# MergeRev4_0.net
KiCad netlist of a schematic drawn in Altium Designer
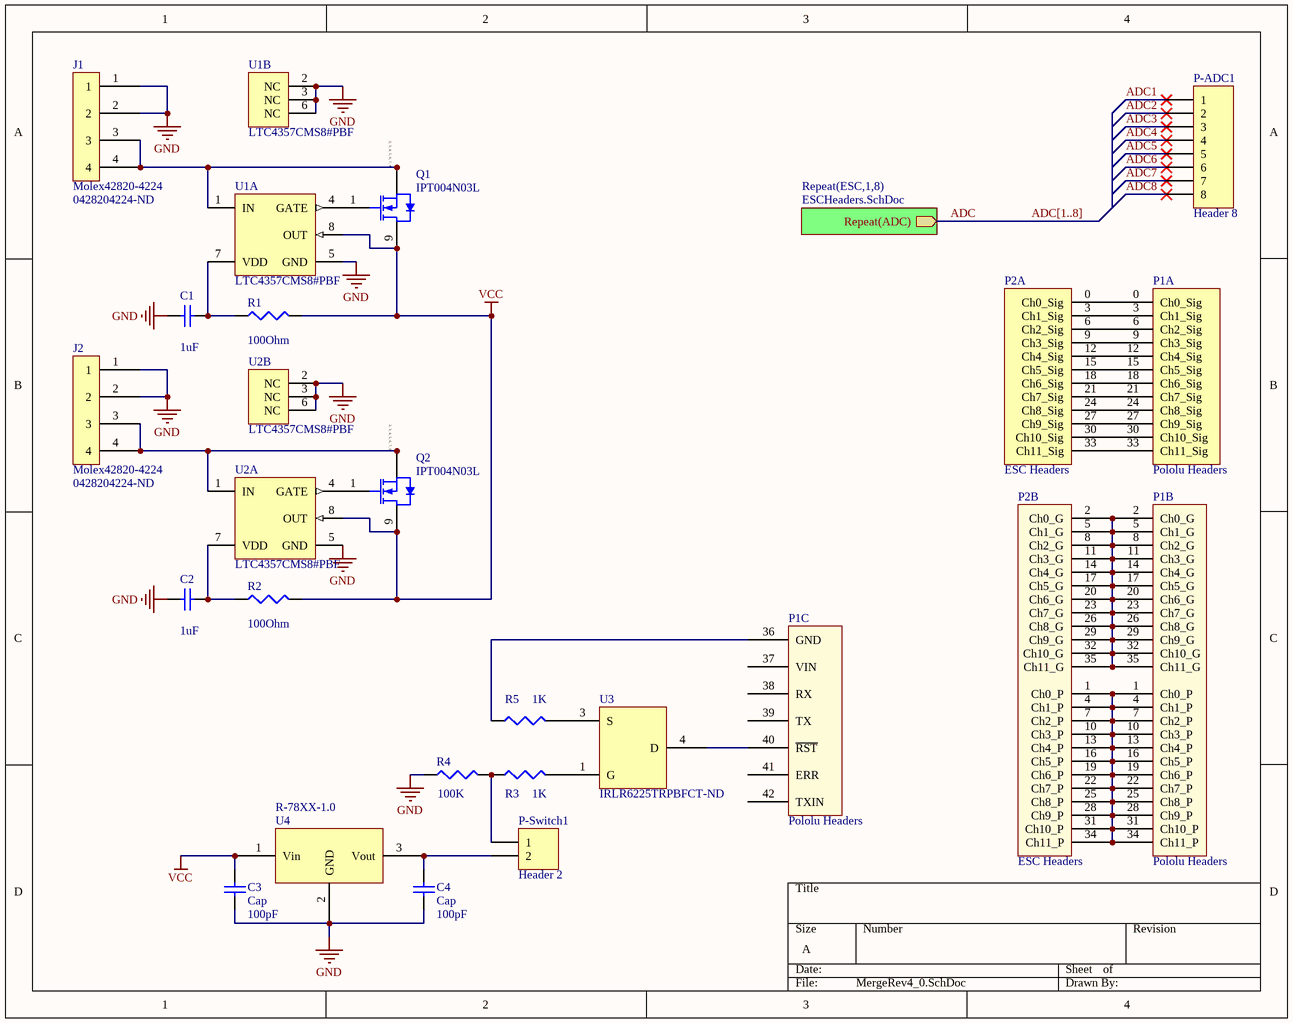
[diagram p0: MergeRev4_0.SchDoc]

(export (version "E")
  (design (tool "Eeschema 10.0.6"))
  (components
    (comp (ref "C1")
      (value "1uF")
      (footprint "C1206")
      (description "Capacitor (Semiconductor SIM Model)")
      (fields (field (name "Comment") "Cap Semi") (field (name "PUBLISHER") "Altium Limited"))
      (libsource (lib "Miscellaneous Devices") (part "Cap Semi"))
    )
    (comp (ref "C2")
      (value "1uF")
      (footprint "C1206")
      (description "Capacitor (Semiconductor SIM Model)")
      (fields (field (name "Comment") "Cap Semi") (field (name "PUBLISHER") "Altium Limited"))
      (libsource (lib "Miscellaneous Devices") (part "Cap Semi"))
    )
    (comp (ref "C3")
      (value "Cap")
      (footprint "1608[0603]")
      (description "Capacitor")
      (fields (field (name "ALTIUM_VALUE") "100pF") (field (name "PUBLISHER") "Altium Limited"))
      (libsource (lib "Miscellaneous Devices") (part "Cap"))
    )
    (comp (ref "C4")
      (value "Cap")
      (footprint "1608[0603]")
      (description "Capacitor")
      (fields (field (name "ALTIUM_VALUE") "100pF") (field (name "PUBLISHER") "Altium Limited"))
      (libsource (lib "Miscellaneous Devices") (part "Cap"))
    )
    (comp (ref "J1")
      (value "Molex42820-4224")
      (footprint "Molex42820-4224")
      (fields (field (name "SUPPLIER PART NUMBER 1") "0428204224-ND"))
      (libsource (lib "Molex42820-4224") (part "Molex42820-4224"))
    )
    (comp (ref "J2")
      (value "Molex42820-4224")
      (footprint "Molex42820-4224")
      (fields (field (name "SUPPLIER PART NUMBER 1") "0428204224-ND"))
      (libsource (lib "Molex42820-4224") (part "Molex42820-4224"))
    )
    (comp (ref "P-ADC1")
      (value "Header 8")
      (footprint "HDR1X8")
      (description "Header, 8-Pin")
      (fields (field (name "PUBLISHER") "Altium Limited"))
      (libsource (lib "Miscellaneous Connectors") (part "Header 8"))
    )
    (comp (ref "P-Switch1")
      (value "Header 2")
      (footprint "HDR1X2")
      (description "Header, 2-Pin")
      (fields (field (name "PUBLISHER") "Altium Limited"))
      (libsource (lib "Miscellaneous Connectors") (part "Header 2"))
    )
    (comp (ref "P1")
      (value "Pololu Headers")
      (footprint "Pololu Headers")
      (libsource (lib "MergeRev3_0") (part "Pololu Headers"))
    )
    (comp (ref "P2")
      (value "ESC Headers")
      (footprint "Pololu Headers")
      (libsource (lib "") (part "Pololu Headers_1"))
    )
    (comp (ref "Q1")
      (value "IPT004N03L")
      (footprint "INF-PG-HSOF-8-1_V")
      (description "N-Channel OptiMOS(TM) Power-MOSFET, 30 V VDS, 300 A ID, -55 to 175 degC, PG-HSOF-8, Reel, Green")
      (fields (field (name "MANUFACTURER") "Infineon"))
      (libsource (lib "MergeRev3_0") (part "IPT004N03L"))
    )
    (comp (ref "Q2")
      (value "IPT004N03L")
      (footprint "INF-PG-HSOF-8-1_V")
      (description "N-Channel OptiMOS(TM) Power-MOSFET, 30 V VDS, 300 A ID, -55 to 175 degC, PG-HSOF-8, Reel, Green")
      (fields (field (name "MANUFACTURER") "Infineon"))
      (libsource (lib "MergeRev3_0") (part "IPT004N03L"))
    )
    (comp (ref "R1")
      (value "100Ohm")
      (footprint "J1-0603")
      (description "Resistor")
      (fields (field (name "Comment") "Res3") (field (name "PUBLISHER") "Altium Limited"))
      (libsource (lib "Miscellaneous Devices") (part "Res3"))
    )
    (comp (ref "R2")
      (value "100Ohm")
      (footprint "J1-0603")
      (description "Resistor")
      (fields (field (name "Comment") "Res3") (field (name "PUBLISHER") "Altium Limited"))
      (libsource (lib "Miscellaneous Devices") (part "Res3"))
    )
    (comp (ref "R3")
      (value "1K")
      (footprint "J1-0603")
      (description "Resistor")
      (fields (field (name "Comment") "Res3") (field (name "PUBLISHER") "Altium Limited"))
      (libsource (lib "Miscellaneous Devices") (part "Res3"))
    )
    (comp (ref "R4")
      (value "100K")
      (footprint "J1-0603")
      (description "Resistor")
      (fields (field (name "Comment") "Res3") (field (name "PUBLISHER") "Altium Limited"))
      (libsource (lib "Miscellaneous Devices") (part "Res3"))
    )
    (comp (ref "R5")
      (value "1K")
      (footprint "J1-0603")
      (description "Resistor")
      (fields (field (name "Comment") "Res3") (field (name "PUBLISHER") "Altium Limited"))
      (libsource (lib "Miscellaneous Devices") (part "Res3"))
    )
    (comp (ref "U1")
      (value "LTC4357CMS8#PBF")
      (footprint "LT-MS8-8_N")
      (fields (field (name "MANUFACTURER") "Linear Technology"))
      (libsource (lib "MergeRev3_0") (part "LTC4357CMS8#PBF"))
    )
    (comp (ref "U2")
      (value "LTC4357CMS8#PBF")
      (footprint "LT-MS8-8_N")
      (fields (field (name "MANUFACTURER") "Linear Technology"))
      (libsource (lib "MergeRev3_0") (part "LTC4357CMS8#PBF"))
    )
    (comp (ref "U3")
      (value "IRLR6225TRPBFCT-ND")
      (footprint "IRLR6225_DT")
      (libsource (lib "IRLR6225_DT") (part "IRLR6225TRPBFCT-ND"))
    )
    (comp (ref "U4")
      (value "R-78XX-1.0")
      (footprint "R-785.0-1.0")
      (libsource (lib "RECOM-Reg") (part "R-78XX-1.0"))
    )
  )
  (nets
    (net (code "2") (name "/ADC1") (class "Default")
      (node (ref "P-ADC1") (pin "1") (pinfunction "1_1") (pintype "passive+no_connect"))
    )
    (net (code "3") (name "/ADC2") (class "Default")
      (node (ref "P-ADC1") (pin "2") (pinfunction "2_2") (pintype "passive+no_connect"))
    )
    (net (code "4") (name "/ADC3") (class "Default")
      (node (ref "P-ADC1") (pin "3") (pinfunction "3_3") (pintype "passive+no_connect"))
    )
    (net (code "5") (name "/ADC4") (class "Default")
      (node (ref "P-ADC1") (pin "4") (pinfunction "4_4") (pintype "passive+no_connect"))
    )
    (net (code "6") (name "/ADC5") (class "Default")
      (node (ref "P-ADC1") (pin "5") (pinfunction "5_5") (pintype "passive+no_connect"))
    )
    (net (code "7") (name "/ADC6") (class "Default")
      (node (ref "P-ADC1") (pin "6") (pinfunction "6_6") (pintype "passive+no_connect"))
    )
    (net (code "8") (name "/ADC7") (class "Default")
      (node (ref "P-ADC1") (pin "7") (pinfunction "7_7") (pintype "passive+no_connect"))
    )
    (net (code "9") (name "/ADC8") (class "Default")
      (node (ref "P-ADC1") (pin "8") (pinfunction "8_8") (pintype "passive+no_connect"))
    )
    (net (code "11") (name "GND") (class "Default")
      (node (ref "C1") (pin "1") (pinfunction "1_1") (pintype "passive"))
      (node (ref "C2") (pin "1") (pinfunction "1_1") (pintype "passive"))
      (node (ref "C3") (pin "1") (pinfunction "1_1") (pintype "passive"))
      (node (ref "C4") (pin "1") (pinfunction "1_1") (pintype "passive"))
      (node (ref "J1") (pin "1") (pinfunction "1_1") (pintype "power_in"))
      (node (ref "J1") (pin "2") (pinfunction "2_2") (pintype "power_in"))
      (node (ref "J2") (pin "1") (pinfunction "1_1") (pintype "power_in"))
      (node (ref "J2") (pin "2") (pinfunction "2_2") (pintype "power_in"))
      (node (ref "R4") (pin "1") (pinfunction "1_1") (pintype "passive"))
      (node (ref "U1") (pin "2") (pinfunction "NC_2") (pintype "passive"))
      (node (ref "U1") (pin "3") (pinfunction "NC_3") (pintype "passive"))
      (node (ref "U1") (pin "5") (pinfunction "GND_5") (pintype "power_in"))
      (node (ref "U1") (pin "6") (pinfunction "NC_6") (pintype "passive"))
      (node (ref "U2") (pin "2") (pinfunction "NC_2") (pintype "passive"))
      (node (ref "U2") (pin "3") (pinfunction "NC_3") (pintype "passive"))
      (node (ref "U2") (pin "5") (pinfunction "GND_5") (pintype "power_in"))
      (node (ref "U2") (pin "6") (pinfunction "NC_6") (pintype "passive"))
      (node (ref "U4") (pin "2") (pinfunction "GND_2") (pintype "passive"))
    )
    (net (code "12") (name "Net-(P-Switch1-Pad1)") (class "Default")
      (node (ref "P-Switch1") (pin "1") (pinfunction "1_1") (pintype "passive"))
      (node (ref "R3") (pin "1") (pinfunction "1_1") (pintype "passive"))
      (node (ref "R4") (pin "2") (pinfunction "2_2") (pintype "passive"))
    )
    (net (code "13") (name "Net-(P1A-Ch0_Sig)") (class "Default")
      (node (ref "P1") (pin "0") (pinfunction "Ch0_Sig_0") (pintype "passive"))
      (node (ref "P2") (pin "0") (pinfunction "Ch0_Sig_0") (pintype "passive"))
    )
    (net (code "14") (name "Net-(P1A-Ch1_Sig)") (class "Default")
      (node (ref "P1") (pin "3") (pinfunction "Ch1_Sig_3") (pintype "passive"))
      (node (ref "P2") (pin "3") (pinfunction "Ch1_Sig_3") (pintype "passive"))
    )
    (net (code "15") (name "Net-(P1A-Ch2_Sig)") (class "Default")
      (node (ref "P1") (pin "6") (pinfunction "Ch2_Sig_6") (pintype "passive"))
      (node (ref "P2") (pin "6") (pinfunction "Ch2_Sig_6") (pintype "passive"))
    )
    (net (code "16") (name "Net-(P1A-Ch3_Sig)") (class "Default")
      (node (ref "P1") (pin "9") (pinfunction "Ch3_Sig_9") (pintype "passive"))
      (node (ref "P2") (pin "9") (pinfunction "Ch3_Sig_9") (pintype "passive"))
    )
    (net (code "17") (name "Net-(P1A-Ch4_Sig)") (class "Default")
      (node (ref "P1") (pin "12") (pinfunction "Ch4_Sig_12") (pintype "passive"))
      (node (ref "P2") (pin "12") (pinfunction "Ch4_Sig_12") (pintype "passive"))
    )
    (net (code "18") (name "Net-(P1A-Ch5_Sig)") (class "Default")
      (node (ref "P1") (pin "15") (pinfunction "Ch5_Sig_15") (pintype "passive"))
      (node (ref "P2") (pin "15") (pinfunction "Ch5_Sig_15") (pintype "passive"))
    )
    (net (code "19") (name "Net-(P1A-Ch6_Sig)") (class "Default")
      (node (ref "P1") (pin "18") (pinfunction "Ch6_Sig_18") (pintype "passive"))
      (node (ref "P2") (pin "18") (pinfunction "Ch6_Sig_18") (pintype "passive"))
    )
    (net (code "20") (name "Net-(P1A-Ch7_Sig)") (class "Default")
      (node (ref "P1") (pin "21") (pinfunction "Ch7_Sig_21") (pintype "passive"))
      (node (ref "P2") (pin "21") (pinfunction "Ch7_Sig_21") (pintype "passive"))
    )
    (net (code "21") (name "Net-(P1A-Ch8_Sig)") (class "Default")
      (node (ref "P1") (pin "24") (pinfunction "Ch8_Sig_24") (pintype "passive"))
      (node (ref "P2") (pin "24") (pinfunction "Ch8_Sig_24") (pintype "passive"))
    )
    (net (code "22") (name "Net-(P1A-Ch9_Sig)") (class "Default")
      (node (ref "P1") (pin "27") (pinfunction "Ch9_Sig_27") (pintype "passive"))
      (node (ref "P2") (pin "27") (pinfunction "Ch9_Sig_27") (pintype "passive"))
    )
    (net (code "23") (name "Net-(P1A-Ch10_Sig)") (class "Default")
      (node (ref "P1") (pin "30") (pinfunction "Ch10_Sig_30") (pintype "passive"))
      (node (ref "P2") (pin "30") (pinfunction "Ch10_Sig_30") (pintype "passive"))
    )
    (net (code "24") (name "Net-(P1A-Ch11_Sig)") (class "Default")
      (node (ref "P1") (pin "33") (pinfunction "Ch11_Sig_33") (pintype "passive"))
      (node (ref "P2") (pin "33") (pinfunction "Ch11_Sig_33") (pintype "passive"))
    )
    (net (code "25") (name "Net-(P1B-Ch0_G)") (class "Default")
      (node (ref "P1") (pin "11") (pinfunction "Ch3_G_11") (pintype "passive"))
      (node (ref "P1") (pin "14") (pinfunction "Ch4_G_14") (pintype "passive"))
      (node (ref "P1") (pin "17") (pinfunction "Ch5_G_17") (pintype "passive"))
      (node (ref "P1") (pin "2") (pinfunction "Ch0_G_2") (pintype "passive"))
      (node (ref "P1") (pin "20") (pinfunction "Ch6_G_20") (pintype "passive"))
      (node (ref "P1") (pin "23") (pinfunction "Ch7_G_23") (pintype "passive"))
      (node (ref "P1") (pin "26") (pinfunction "Ch8_G_26") (pintype "passive"))
      (node (ref "P1") (pin "29") (pinfunction "Ch9_G_29") (pintype "passive"))
      (node (ref "P1") (pin "32") (pinfunction "Ch10_G_32") (pintype "passive"))
      (node (ref "P1") (pin "35") (pinfunction "Ch11_G_35") (pintype "passive"))
      (node (ref "P1") (pin "5") (pinfunction "Ch1_G_5") (pintype "passive"))
      (node (ref "P1") (pin "8") (pinfunction "Ch2_G_8") (pintype "passive"))
      (node (ref "P2") (pin "11") (pinfunction "Ch3_G_11") (pintype "passive"))
      (node (ref "P2") (pin "14") (pinfunction "Ch4_G_14") (pintype "passive"))
      (node (ref "P2") (pin "17") (pinfunction "Ch5_G_17") (pintype "passive"))
      (node (ref "P2") (pin "2") (pinfunction "Ch0_G_2") (pintype "passive"))
      (node (ref "P2") (pin "20") (pinfunction "Ch6_G_20") (pintype "passive"))
      (node (ref "P2") (pin "23") (pinfunction "Ch7_G_23") (pintype "passive"))
      (node (ref "P2") (pin "26") (pinfunction "Ch8_G_26") (pintype "passive"))
      (node (ref "P2") (pin "29") (pinfunction "Ch9_G_29") (pintype "passive"))
      (node (ref "P2") (pin "32") (pinfunction "Ch10_G_32") (pintype "passive"))
      (node (ref "P2") (pin "35") (pinfunction "Ch11_G_35") (pintype "passive"))
      (node (ref "P2") (pin "5") (pinfunction "Ch1_G_5") (pintype "passive"))
      (node (ref "P2") (pin "8") (pinfunction "Ch2_G_8") (pintype "passive"))
    )
    (net (code "26") (name "Net-(P1B-Ch0_P)") (class "Default")
      (node (ref "P1") (pin "1") (pinfunction "Ch0_P_1") (pintype "passive"))
      (node (ref "P1") (pin "10") (pinfunction "Ch3_P_10") (pintype "passive"))
      (node (ref "P1") (pin "13") (pinfunction "Ch4_P_13") (pintype "passive"))
      (node (ref "P1") (pin "16") (pinfunction "Ch5_P_16") (pintype "passive"))
      (node (ref "P1") (pin "19") (pinfunction "Ch6_P_19") (pintype "passive"))
      (node (ref "P1") (pin "22") (pinfunction "Ch7_P_22") (pintype "passive"))
      (node (ref "P1") (pin "25") (pinfunction "Ch8_P_25") (pintype "passive"))
      (node (ref "P1") (pin "28") (pinfunction "Ch9_P_28") (pintype "passive"))
      (node (ref "P1") (pin "31") (pinfunction "Ch10_P_31") (pintype "passive"))
      (node (ref "P1") (pin "34") (pinfunction "Ch11_P_34") (pintype "passive"))
      (node (ref "P1") (pin "4") (pinfunction "Ch1_P_4") (pintype "passive"))
      (node (ref "P1") (pin "7") (pinfunction "Ch2_P_7") (pintype "passive"))
      (node (ref "P2") (pin "1") (pinfunction "Ch0_P_1") (pintype "passive"))
      (node (ref "P2") (pin "10") (pinfunction "Ch3_P_10") (pintype "passive"))
      (node (ref "P2") (pin "13") (pinfunction "Ch4_P_13") (pintype "passive"))
      (node (ref "P2") (pin "16") (pinfunction "Ch5_P_16") (pintype "passive"))
      (node (ref "P2") (pin "19") (pinfunction "Ch6_P_19") (pintype "passive"))
      (node (ref "P2") (pin "22") (pinfunction "Ch7_P_22") (pintype "passive"))
      (node (ref "P2") (pin "25") (pinfunction "Ch8_P_25") (pintype "passive"))
      (node (ref "P2") (pin "28") (pinfunction "Ch9_P_28") (pintype "passive"))
      (node (ref "P2") (pin "31") (pinfunction "Ch10_P_31") (pintype "passive"))
      (node (ref "P2") (pin "34") (pinfunction "Ch11_P_34") (pintype "passive"))
      (node (ref "P2") (pin "4") (pinfunction "Ch1_P_4") (pintype "passive"))
      (node (ref "P2") (pin "7") (pinfunction "Ch2_P_7") (pintype "passive"))
    )
    (net (code "27") (name "Net-(P1C-GND)") (class "Default")
      (node (ref "P1") (pin "36") (pinfunction "GND_36") (pintype "passive"))
      (node (ref "R5") (pin "1") (pinfunction "1_1") (pintype "passive"))
    )
    (net (code "28") (name "Net-(P1C-~{RST})") (class "Default")
      (node (ref "P1") (pin "40") (pinfunction "~{RST}_40") (pintype "passive"))
      (node (ref "U3") (pin "4") (pinfunction "D_4") (pintype "passive"))
    )
    (net (code "29") (name "Net-(Q1-GATE)") (class "Default")
      (node (ref "Q1") (pin "1") (pinfunction "GATE_1") (pintype "passive"))
      (node (ref "U1") (pin "4") (pinfunction "GATE_4") (pintype "output"))
    )
    (net (code "30") (name "Net-(Q2-GATE)") (class "Default")
      (node (ref "Q2") (pin "1") (pinfunction "GATE_1") (pintype "passive"))
      (node (ref "U2") (pin "4") (pinfunction "GATE_4") (pintype "output"))
    )
    (net (code "31") (name "Net-(U1A-IN)") (class "Default")
      (node (ref "J1") (pin "3") (pinfunction "3_3") (pintype "power_in"))
      (node (ref "J1") (pin "4") (pinfunction "4_4") (pintype "power_in"))
      (node (ref "Q1") (pin "2") (pinfunction "S_2") (pintype "passive"))
      (node (ref "Q1") (pin "3") (pinfunction "S_3") (pintype "passive"))
      (node (ref "Q1") (pin "4") (pinfunction "S_4") (pintype "passive"))
      (node (ref "Q1") (pin "5") (pinfunction "S_5") (pintype "passive"))
      (node (ref "Q1") (pin "6") (pinfunction "S_6") (pintype "passive"))
      (node (ref "Q1") (pin "7") (pinfunction "S_7") (pintype "passive"))
      (node (ref "Q1") (pin "8") (pinfunction "S_8") (pintype "passive"))
      (node (ref "U1") (pin "1") (pinfunction "IN_1") (pintype "power_in"))
    )
    (net (code "32") (name "Net-(U1A-VDD)") (class "Default")
      (node (ref "C1") (pin "2") (pinfunction "2_2") (pintype "passive"))
      (node (ref "R1") (pin "1") (pinfunction "1_1") (pintype "passive"))
      (node (ref "U1") (pin "7") (pinfunction "VDD_7") (pintype "power_in"))
    )
    (net (code "33") (name "Net-(U2A-IN)") (class "Default")
      (node (ref "J2") (pin "3") (pinfunction "3_3") (pintype "power_in"))
      (node (ref "J2") (pin "4") (pinfunction "4_4") (pintype "power_in"))
      (node (ref "Q2") (pin "2") (pinfunction "S_2") (pintype "passive"))
      (node (ref "Q2") (pin "3") (pinfunction "S_3") (pintype "passive"))
      (node (ref "Q2") (pin "4") (pinfunction "S_4") (pintype "passive"))
      (node (ref "Q2") (pin "5") (pinfunction "S_5") (pintype "passive"))
      (node (ref "Q2") (pin "6") (pinfunction "S_6") (pintype "passive"))
      (node (ref "Q2") (pin "7") (pinfunction "S_7") (pintype "passive"))
      (node (ref "Q2") (pin "8") (pinfunction "S_8") (pintype "passive"))
      (node (ref "U2") (pin "1") (pinfunction "IN_1") (pintype "power_in"))
    )
    (net (code "34") (name "Net-(U2A-VDD)") (class "Default")
      (node (ref "C2") (pin "2") (pinfunction "2_2") (pintype "passive"))
      (node (ref "R2") (pin "1") (pinfunction "1_1") (pintype "passive"))
      (node (ref "U2") (pin "7") (pinfunction "VDD_7") (pintype "power_in"))
    )
    (net (code "35") (name "Net-(U3-G)") (class "Default")
      (node (ref "R3") (pin "2") (pinfunction "2_2") (pintype "passive"))
      (node (ref "U3") (pin "1") (pinfunction "G_1") (pintype "passive"))
    )
    (net (code "36") (name "Net-(U3-S)") (class "Default")
      (node (ref "R5") (pin "2") (pinfunction "2_2") (pintype "passive"))
      (node (ref "U3") (pin "3") (pinfunction "S_3") (pintype "passive"))
    )
    (net (code "37") (name "Net-(U4-Vout)") (class "Default")
      (node (ref "C4") (pin "2") (pinfunction "2_2") (pintype "passive"))
      (node (ref "P-Switch1") (pin "2") (pinfunction "2_2") (pintype "passive"))
      (node (ref "U4") (pin "3") (pinfunction "Vout_3") (pintype "passive"))
    )
    (net (code "38") (name "VCC") (class "Default")
      (node (ref "C3") (pin "2") (pinfunction "2_2") (pintype "passive"))
      (node (ref "Q1") (pin "9") (pinfunction "D_9") (pintype "passive"))
      (node (ref "Q2") (pin "9") (pinfunction "D_9") (pintype "passive"))
      (node (ref "R1") (pin "2") (pinfunction "2_2") (pintype "passive"))
      (node (ref "R2") (pin "2") (pinfunction "2_2") (pintype "passive"))
      (node (ref "U1") (pin "8") (pinfunction "OUT_8") (pintype "input"))
      (node (ref "U2") (pin "8") (pinfunction "OUT_8") (pintype "input"))
      (node (ref "U4") (pin "1") (pinfunction "Vin_1") (pintype "passive"))
    )
    (net (code "39") (name "unconnected-(P1C-ERR-Pad41)") (class "Default")
      (node (ref "P1") (pin "41") (pinfunction "ERR_41") (pintype "passive"))
    )
    (net (code "40") (name "unconnected-(P1C-RX-Pad38)") (class "Default")
      (node (ref "P1") (pin "38") (pinfunction "RX_38") (pintype "passive"))
    )
    (net (code "41") (name "unconnected-(P1C-TX-Pad39)") (class "Default")
      (node (ref "P1") (pin "39") (pinfunction "TX_39") (pintype "passive"))
    )
    (net (code "42") (name "unconnected-(P1C-TXIN-Pad42)") (class "Default")
      (node (ref "P1") (pin "42") (pinfunction "TXIN_42") (pintype "passive"))
    )
    (net (code "43") (name "unconnected-(P1C-VIN-Pad37)") (class "Default")
      (node (ref "P1") (pin "37") (pinfunction "VIN_37") (pintype "passive"))
    )
  )
)
